# design.net
KiCad netlist of a schematic drawn in Altium Designer
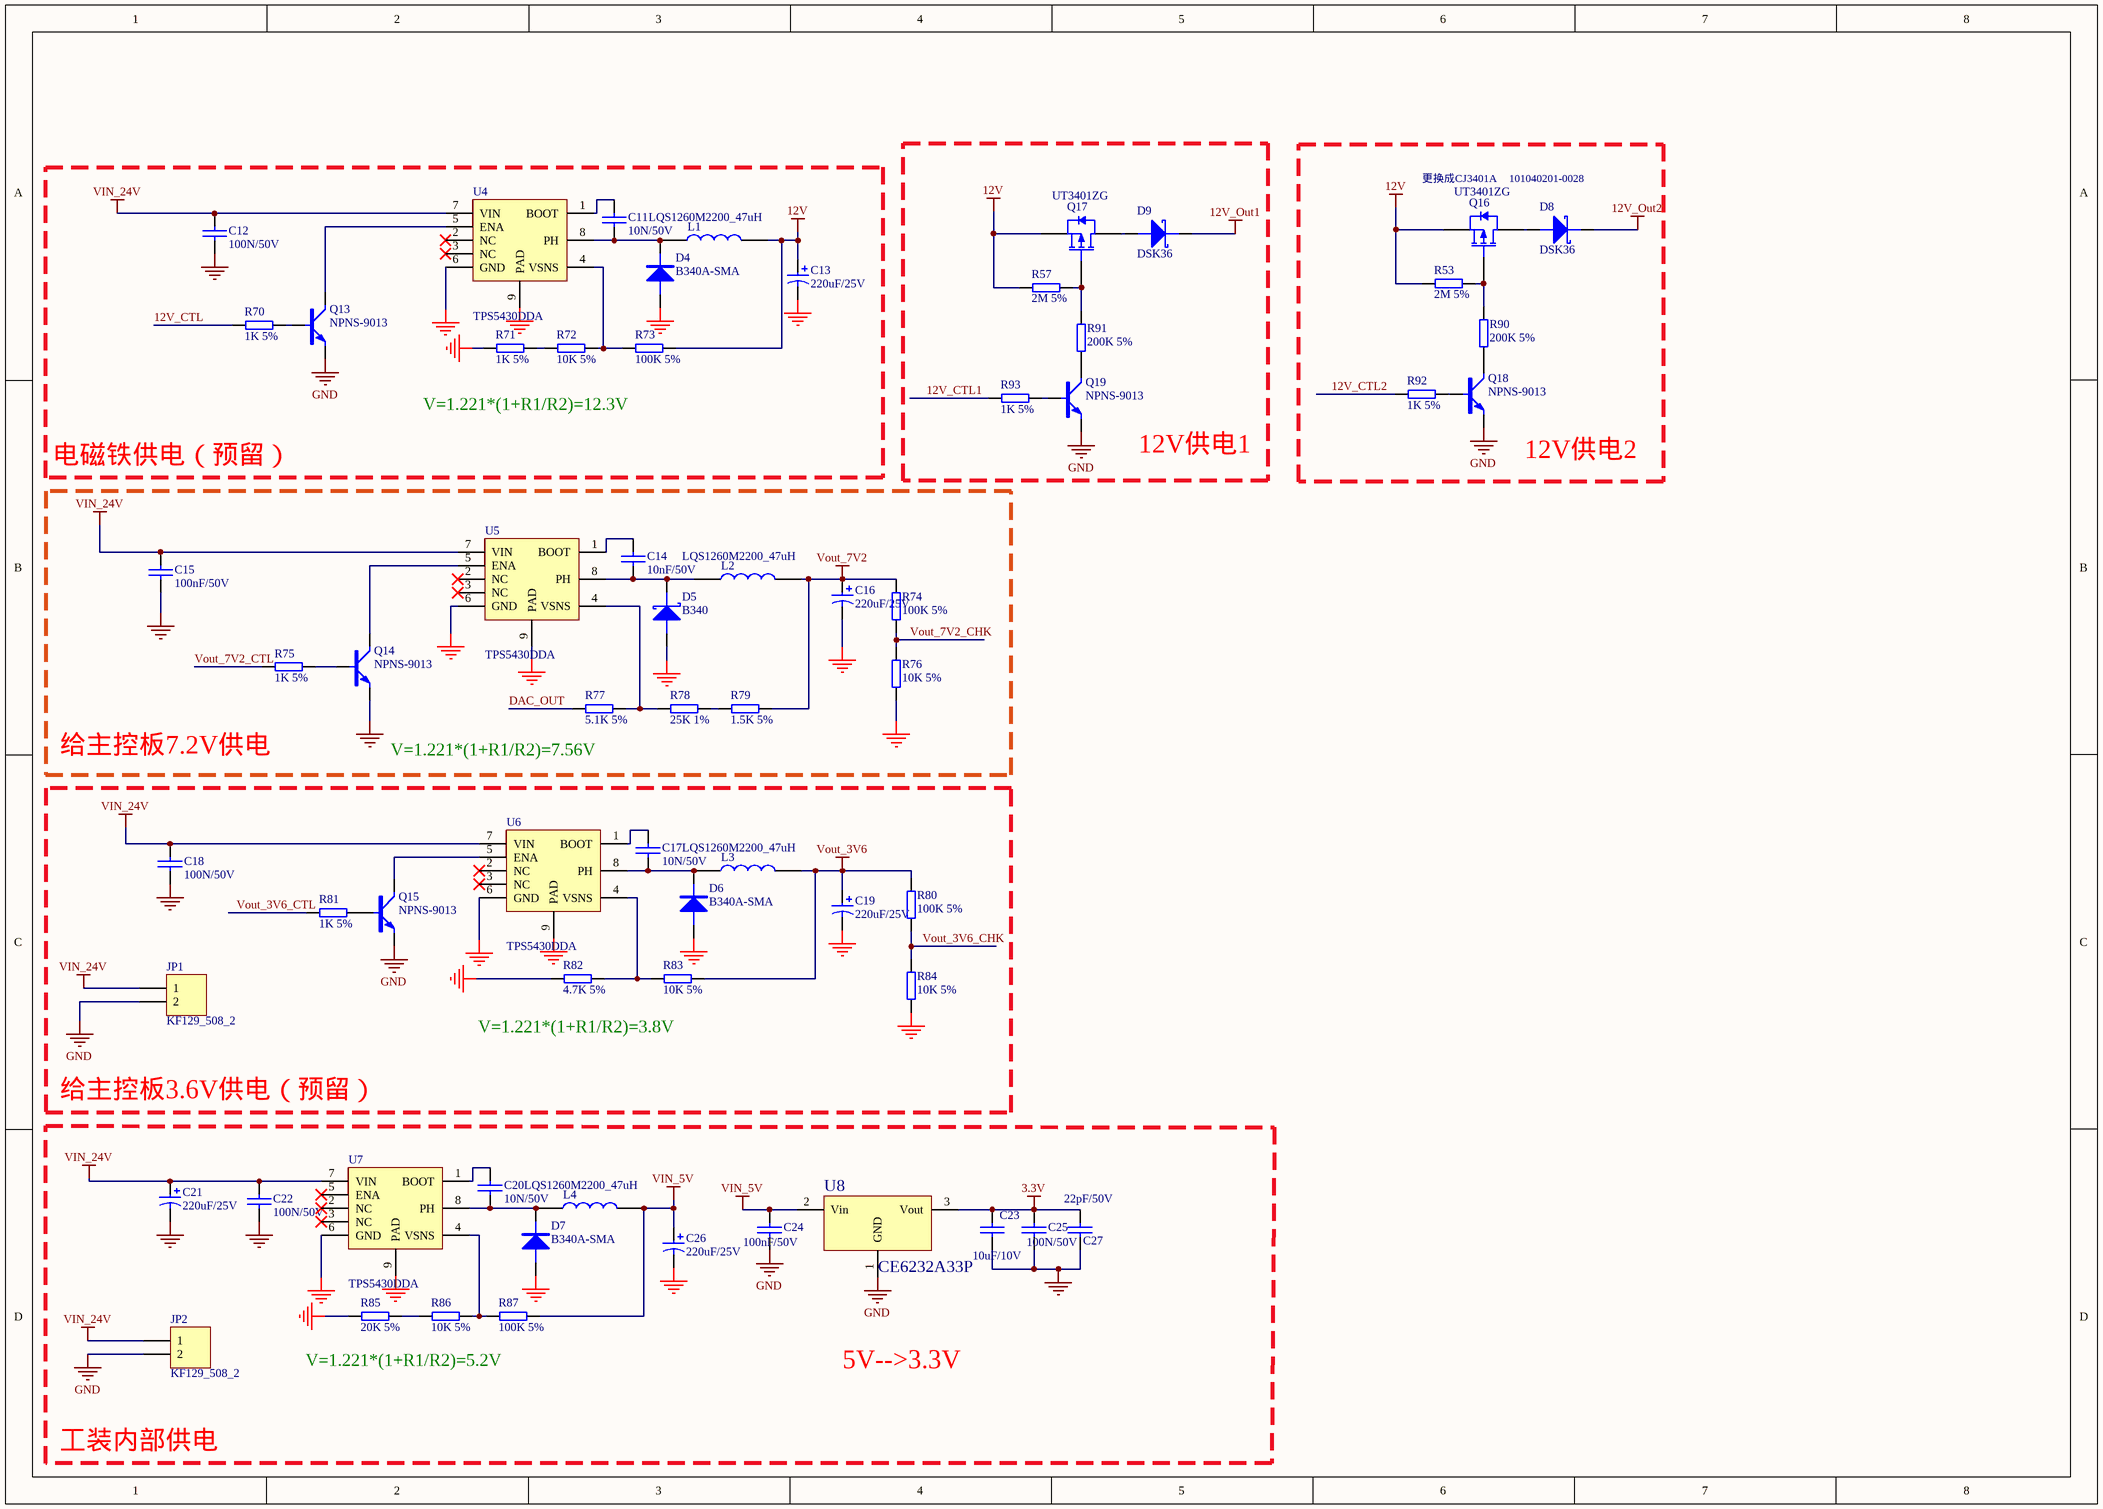
[diagram p0: 电源.SchDoc]

(export (version "E")
  (design (tool "Eeschema 10.0.6"))
  (components
    (comp (ref "C11")
      (value "10N/50V")
      (footprint "CAP0603")
      (description "10N/50V，±10%，0603")
      (fields (field (name "PART NUMBER") "101020103-0007"))
      (libsource (lib "Database_Libs1") (part "CC03K7R9B_10N"))
    )
    (comp (ref "C12")
      (value "100N/50V")
      (footprint "CAP0603")
      (description "100N/50V，±10%，0603")
      (fields (field (name "PART NUMBER") "101020103-0021"))
      (libsource (lib "Database_Libs1") (part "CC03K7R9B_100N"))
    )
    (comp (ref "C13")
      (value "220uF/25V")
      (footprint "220uF 25V")
      (description "220UF,25 V,±20%,8*10mm,立隆电子工业股份有限公司,VEJ221M1ETR-0810")
      (libsource (lib "转接板封装") (part "220uF/25V"))
    )
    (comp (ref "C14")
      (value "10nF/50V")
      (footprint "CAP0603")
      (description "10nF,50 V,±10%,0603,X7R,国巨,CC0603KRX7R9BB103")
      (fields (field (name "PART NUMBER") "101020103-0007"))
      (libsource (lib "Database_Libs2") (part "CC03K7R9_103P"))
    )
    (comp (ref "C15")
      (value "100nF/50V")
      (footprint "CAP0603")
      (description "104pF,50 V,±10%,0603,国巨,CC0603KRX7R9BB104")
      (fields (field (name "PART NUMBER") "101020103-0021"))
      (libsource (lib "Database_Libs2") (part "CC03K7R9_100N"))
    )
    (comp (ref "C16")
      (value "220uF/25V")
      (footprint "220uF 25V")
      (description "220UF,25 V,±20%,8*10mm,立隆电子工业股份有限公司,VEJ221M1ETR-0810")
      (libsource (lib "转接板封装") (part "220uF/25V"))
    )
    (comp (ref "C17")
      (value "10N/50V")
      (footprint "CAP0603")
      (description "10N/50V，±10%，0603")
      (fields (field (name "PART NUMBER") "101020103-0007"))
      (libsource (lib "Database_Libs1") (part "CC03K7R9B_10N"))
    )
    (comp (ref "C18")
      (value "100N/50V")
      (footprint "CAP0603")
      (description "100N/50V，±10%，0603")
      (fields (field (name "PART NUMBER") "101020103-0021"))
      (libsource (lib "Database_Libs1") (part "CC03K7R9B_100N"))
    )
    (comp (ref "C19")
      (value "220uF/25V")
      (footprint "220uF 25V")
      (description "220UF,25 V,±20%,8*10mm,立隆电子工业股份有限公司,VEJ221M1ETR-0810")
      (libsource (lib "转接板封装") (part "220uF/25V"))
    )
    (comp (ref "C20")
      (value "10N/50V")
      (footprint "CAP0603")
      (description "10N/50V，±10%，0603")
      (fields (field (name "PART NUMBER") "101020103-0007"))
      (libsource (lib "Database_Libs1") (part "CC03K7R9B_10N"))
    )
    (comp (ref "C21")
      (value "220uF/25V")
      (footprint "220uF 25V")
      (description "220UF,25 V,±20%,8*10mm,立隆电子工业股份有限公司,VEJ221M1ETR-0810")
      (libsource (lib "转接板封装") (part "220uF/25V"))
    )
    (comp (ref "C22")
      (value "100N/50V")
      (footprint "CAP0603")
      (description "100N/50V，±10%，0603")
      (fields (field (name "PART NUMBER") "101020103-0021"))
      (libsource (lib "Database_Libs1") (part "CC03K7R9B_100N"))
    )
    (comp (ref "C23")
      (value "10uF/10V")
      (footprint "CAP0603")
      (description "106pF,10 V,±10%,0603,村田,GRM188R61A106KE47D")
      (fields (field (name "PART NUMBER") "101020103-0026"))
      (libsource (lib "Database_Libs2") (part "CC03K5R6_10U"))
    )
    (comp (ref "C24")
      (value "100nF/50V")
      (footprint "CAP0603")
      (description "104pF,50 V,±10%,0603,国巨,CC0603KRX7R9BB104")
      (fields (field (name "PART NUMBER") "101020103-0021"))
      (libsource (lib "Database_Libs2") (part "CC03K7R9_100N"))
    )
    (comp (ref "C25")
      (value "100N/50V")
      (footprint "CAP0603")
      (description "100N/50V，±10%，0603")
      (fields (field (name "PART NUMBER") "101020103-0021"))
      (libsource (lib "Database_Libs2") (part "CC03K7R9B_100N"))
    )
    (comp (ref "C26")
      (value "220uF/25V")
      (footprint "220uF 25V")
      (description "220UF,25 V,±20%,8*10mm,立隆电子工业股份有限公司,VEJ221M1ETR-0810")
      (libsource (lib "转接板封装") (part "220uF/25V"))
    )
    (comp (ref "C27")
      (value "22pF/50V")
      (footprint "CAP0603")
      (description "22pF,50 V,±5%,0603,国巨,CC0603JRNPO9BN22")
      (fields (field (name "PART NUMBER") "101020103-0009"))
      (libsource (lib "Database_Libs2") (part "CC03JPO9_22P"))
    )
    (comp (ref "D4")
      (value "B340A-SMA")
      (footprint "DO-214AC")
      (fields (field (name "PART NUMBER") "101040101-0014"))
      (libsource (lib "Database_Libs1") (part "02_B340A-SMA"))
    )
    (comp (ref "D5")
      (value "B340")
      (footprint "DO-214AC")
      (description "B340,SMA,3 A,0.7 V,28 V,DIODES,B340A-13-F")
      (fields (field (name "PART NUMBER") "101040101-0014"))
      (libsource (lib "Database_Libs2") (part "02_B340"))
    )
    (comp (ref "D6")
      (value "B340A-SMA")
      (footprint "DO-214AC")
      (fields (field (name "PART NUMBER") "101040101-0014"))
      (libsource (lib "Database_Libs1") (part "02_B340A-SMA"))
    )
    (comp (ref "D7")
      (value "B340A-SMA")
      (footprint "DO-214AC")
      (fields (field (name "PART NUMBER") "101040101-0014"))
      (libsource (lib "Database_Libs1") (part "02_B340A-SMA"))
    )
    (comp (ref "D8")
      (value "DSK36")
      (footprint "SOD-123FL")
      (description "DSK14,SOD-123FL,1 A,40 V,28 V,台湾强茂集团苏州群鑫电子,DSK14")
      (fields (field (name "PART NUMBER") "101040101-0043"))
      (libsource (lib "Database_Libs2") (part "02_DSK14"))
    )
    (comp (ref "D9")
      (value "DSK36")
      (footprint "SOD-123FL")
      (description "DSK14,SOD-123FL,1 A,40 V,28 V,台湾强茂集团苏州群鑫电子,DSK14")
      (fields (field (name "PART NUMBER") "101040101-0043"))
      (libsource (lib "Database_Libs2") (part "02_DSK14"))
    )
    (comp (ref "JP1")
      (value "KF129_508_2")
      (footprint "KF129_508_2")
      (description "KF129-2P,螺丝紧固,2,ABS,松涛")
      (fields (field (name "PART NUMBER") "1010904-0015"))
      (libsource (lib "Database_Libs2") (part "KF129_508_2"))
    )
    (comp (ref "JP2")
      (value "KF129_508_2")
      (footprint "KF129_508_2")
      (description "KF129-2P,螺丝紧固,2,ABS,松涛")
      (fields (field (name "PART NUMBER") "1010904-0015"))
      (libsource (lib "Database_Libs2") (part "KF129_508_2"))
    )
    (comp (ref "L1")
      (value "LQS1260M2200_47uH")
      (footprint "LQS1212")
      (description "47uH/2.2A,±20%，0.072Ω，L1200X1200X600")
      (fields (field (name "PART NUMBER") "1010302-0007"))
      (libsource (lib "Database_Libs1") (part "06_LQS1260M2200_47uH"))
    )
    (comp (ref "L2")
      (value "LQS1260M2200_47uH")
      (footprint "LQS1212")
      (description "47uH/2.2A,±20%，0.072Ω，L1200X1200X600")
      (fields (field (name "PART NUMBER") "1010302-0007"))
      (libsource (lib "Database_Libs1") (part "06_LQS1260M2200_47uH"))
    )
    (comp (ref "L3")
      (value "LQS1260M2200_47uH")
      (footprint "LQS1212")
      (description "47uH/2.2A,±20%，0.072Ω，L1200X1200X600")
      (fields (field (name "PART NUMBER") "1010302-0007"))
      (libsource (lib "Database_Libs1") (part "06_LQS1260M2200_47uH"))
    )
    (comp (ref "L4")
      (value "LQS1260M2200_47uH")
      (footprint "LQS1212")
      (description "47uH/2.2A,±20%，0.072Ω，L1200X1200X600")
      (fields (field (name "PART NUMBER") "1010302-0007"))
      (libsource (lib "Database_Libs1") (part "06_LQS1260M2200_47uH"))
    )
    (comp (ref "Q13")
      (value "NPNS-9013")
      (footprint "SOT-23")
      (description "9013,NPN,SOT-23,长电,S9013")
      (fields (field (name "PART NUMBER") "101040201-0002"))
      (libsource (lib "Database_Libs2") (part "03_NPNS-9013"))
    )
    (comp (ref "Q14")
      (value "NPNS-9013")
      (footprint "SOT-23")
      (description "9013,NPN,SOT-23,长电,S9013")
      (fields (field (name "PART NUMBER") "101040201-0002"))
      (libsource (lib "Database_Libs2") (part "03_NPNS-9013"))
    )
    (comp (ref "Q15")
      (value "NPNS-9013")
      (footprint "SOT-23")
      (description "9013,NPN,SOT-23,长电,S9013")
      (fields (field (name "PART NUMBER") "101040201-0002"))
      (libsource (lib "Database_Libs2") (part "03_NPNS-9013"))
    )
    (comp (ref "Q16")
      (value "UT3401ZG")
      (footprint "SOT-23")
      (description "UT3401ZG,P-MOS,SOT-23,UTC,UT3401ZG")
      (fields (field (name "PART NUMBER") "101040201-0013"))
      (libsource (lib "Database_Libs2") (part "03_P-UT3401ZG"))
    )
    (comp (ref "Q17")
      (value "UT3401ZG")
      (footprint "SOT-23")
      (description "UT3401ZG,P-MOS,SOT-23,UTC,UT3401ZG")
      (fields (field (name "PART NUMBER") "101040201-0013"))
      (libsource (lib "Database_Libs2") (part "03_P-UT3401ZG"))
    )
    (comp (ref "Q18")
      (value "NPNS-9013")
      (footprint "SOT-23")
      (description "9013,NPN,SOT-23,长电,S9013")
      (fields (field (name "PART NUMBER") "101040201-0002"))
      (libsource (lib "Database_Libs2") (part "03_NPNS-9013"))
    )
    (comp (ref "Q19")
      (value "NPNS-9013")
      (footprint "SOT-23")
      (description "9013,NPN,SOT-23,长电,S9013")
      (fields (field (name "PART NUMBER") "101040201-0002"))
      (libsource (lib "Database_Libs2") (part "03_NPNS-9013"))
    )
    (comp (ref "R53")
      (value "2M 5%")
      (footprint "RES0603")
      (description "国巨,±5%,0603,,155 ℃,-55 ℃,RC0603JR-072ML,含铅,100 ppm/℃,1/10W,,2M")
      (fields (field (name "PART NUMBER") "101010103-0025"))
      (libsource (lib "Database_Libs2") (part "RC03J_2M"))
    )
    (comp (ref "R57")
      (value "2M 5%")
      (footprint "RES0603")
      (description "国巨,±5%,0603,,155 ℃,-55 ℃,RC0603JR-072ML,含铅,100 ppm/℃,1/10W,,2M")
      (fields (field (name "PART NUMBER") "101010103-0025"))
      (libsource (lib "Database_Libs2") (part "RC03J_2M"))
    )
    (comp (ref "R70")
      (value "1K 5%")
      (footprint "RES0603")
      (description "1K,±5%,1/10W,0603,国巨,RC0603JR-071KL")
      (fields (field (name "PART NUMBER") "101010103-0008"))
      (libsource (lib "Database_Libs2") (part "RC03J_1K"))
    )
    (comp (ref "R71")
      (value "1K 5%")
      (footprint "RES0603")
      (description "1K,±5%,1/10W,0603,国巨,RC0603JR-071KL")
      (fields (field (name "PART NUMBER") "101010103-0008"))
      (libsource (lib "Database_Libs2") (part "RC03J_1K"))
    )
    (comp (ref "R72")
      (value "10K 5%")
      (footprint "RES0603")
      (description "国巨,±5%,0603,,155 ℃,-55 ℃,RC0603JR-0710KL,无铅,200 ppm/℃,1/10W,,10K")
      (fields (field (name "PART NUMBER") "101010103-0003"))
      (libsource (lib "Database_Libs2") (part "RC03J_10K"))
    )
    (comp (ref "R73")
      (value "100K 5%")
      (footprint "RES0603")
      (description "国巨,±5%,0603,,155 ℃,-55 ℃,RC0603JR-07100KL,无铅,100 ppm/℃,1/10W,,100K")
      (fields (field (name "PART NUMBER") "101010103-0005"))
      (libsource (lib "Database_Libs2") (part "RC03J_100K"))
    )
    (comp (ref "R74")
      (value "100K 5%")
      (footprint "RES0603")
      (description "国巨,±5%,0603,,155 ℃,-55 ℃,RC0603JR-07100KL,无铅,100 ppm/℃,1/10W,,100K")
      (fields (field (name "PART NUMBER") "101010103-0005"))
      (libsource (lib "Database_Libs2") (part "RC03J_100K"))
    )
    (comp (ref "R75")
      (value "1K 5%")
      (footprint "RES0603")
      (description "1K,±5%,1/10W,0603,国巨,RC0603JR-071KL")
      (fields (field (name "PART NUMBER") "101010103-0008"))
      (libsource (lib "Database_Libs2") (part "RC03J_1K"))
    )
    (comp (ref "R76")
      (value "10K 5%")
      (footprint "RES0603")
      (description "国巨,±5%,0603,,155 ℃,-55 ℃,RC0603JR-0710KL,无铅,200 ppm/℃,1/10W,,10K")
      (fields (field (name "PART NUMBER") "101010103-0003"))
      (libsource (lib "Database_Libs2") (part "RC03J_10K"))
    )
    (comp (ref "R77")
      (value "5.1K 5%")
      (footprint "RES0603")
      (description "国巨,±5%,0603,,155 ℃,55 ℃,RC0603JR-075.1KL,无铅,200 ppm/℃,1/10W,,5.1k")
      (fields (field (name "PART NUMBER") "101010103-0015"))
      (libsource (lib "Database_Libs2") (part "RC03J_5.1K"))
    )
    (comp (ref "R78")
      (value "25K 1%")
      (footprint "RES0603")
      (description "25K±1%,1/10W,0603")
      (fields (field (name "PART NUMBER") "101010103-0056"))
      (libsource (lib "转接板封装") (part "RC03J_25K"))
    )
    (comp (ref "R79")
      (value "1.5K 5%")
      (footprint "RES0603")
      (description "1.5K,±5%,1/10W,0603,国巨,RC0603JR-071K5L")
      (fields (field (name "PART NUMBER") "101010103-0013"))
      (libsource (lib "转接板封装") (part "RC03J_1.5K"))
    )
    (comp (ref "R80")
      (value "100K 5%")
      (footprint "RES0603")
      (description "100K±5%,1/10W,0603")
      (fields (field (name "PART NUMBER") "101010103-0005"))
      (libsource (lib "Database_Libs1") (part "RC03JF_100K"))
    )
    (comp (ref "R81")
      (value "1K 5%")
      (footprint "RES0603")
      (description "1K,±5%,1/10W,0603,国巨,RC0603JR-071KL")
      (fields (field (name "PART NUMBER") "101010103-0008"))
      (libsource (lib "Database_Libs2") (part "RC03J_1K"))
    )
    (comp (ref "R82")
      (value "4.7K 5%")
      (footprint "RES0603")
      (description "4.7K±5%,1/10W,0603")
      (fields (field (name "PART NUMBER") "101010103-0042"))
      (libsource (lib "Database_Libs2") (part "RC03J_4.7K"))
    )
    (comp (ref "R83")
      (value "10K 5%")
      (footprint "RES0603")
      (description "国巨,±5%,0603,,155 ℃,-55 ℃,RC0603JR-0710KL,无铅,200 ppm/℃,1/10W,,10K")
      (fields (field (name "PART NUMBER") "101010103-0003"))
      (libsource (lib "Database_Libs2") (part "RC03J_10K"))
    )
    (comp (ref "R84")
      (value "10K 5%")
      (footprint "RES0603")
      (description "国巨,±5%,0603,,155 ℃,-55 ℃,RC0603JR-0710KL,无铅,200 ppm/℃,1/10W,,10K")
      (fields (field (name "PART NUMBER") "101010103-0003"))
      (libsource (lib "Database_Libs2") (part "RC03J_10K"))
    )
    (comp (ref "R85")
      (value "20K 5%")
      (footprint "RES0603")
      (description "国巨,±5%,0603,,155 ℃,-55 ℃,RC0603JR-0720KL,无铅,200 ppm/℃,1/10W,,20K")
      (fields (field (name "PART NUMBER") "101010103-0004"))
      (libsource (lib "Database_Libs2") (part "RC03J_20K"))
    )
    (comp (ref "R86")
      (value "10K 5%")
      (footprint "RES0603")
      (description "国巨,±5%,0603,,155 ℃,-55 ℃,RC0603JR-0710KL,无铅,200 ppm/℃,1/10W,,10K")
      (fields (field (name "PART NUMBER") "101010103-0003"))
      (libsource (lib "Database_Libs2") (part "RC03J_10K"))
    )
    (comp (ref "R87")
      (value "100K 5%")
      (footprint "RES0603")
      (description "100K±5%,1/10W,0603")
      (fields (field (name "PART NUMBER") "101010103-0005"))
      (libsource (lib "Database_Libs1") (part "RC03JF_100K"))
    )
    (comp (ref "R90")
      (value "200K 5%")
      (footprint "RES0603")
      (description "200K,±5%,1/10W,0603,国巨,RC0603JR-07200KL")
      (fields (field (name "PART NUMBER") "101010103-0034"))
      (libsource (lib "Database_Libs2") (part "RC03J_200K"))
    )
    (comp (ref "R91")
      (value "200K 5%")
      (footprint "RES0603")
      (description "200K,±5%,1/10W,0603,国巨,RC0603JR-07200KL")
      (fields (field (name "PART NUMBER") "101010103-0034"))
      (libsource (lib "Database_Libs2") (part "RC03J_200K"))
    )
    (comp (ref "R92")
      (value "1K 5%")
      (footprint "RES0603")
      (description "1K,±5%,1/10W,0603,国巨,RC0603JR-071KL")
      (fields (field (name "PART NUMBER") "101010103-0008"))
      (libsource (lib "Database_Libs2") (part "RC03J_1K"))
    )
    (comp (ref "R93")
      (value "1K 5%")
      (footprint "RES0603")
      (description "1K,±5%,1/10W,0603,国巨,RC0603JR-071KL")
      (fields (field (name "PART NUMBER") "101010103-0008"))
      (libsource (lib "Database_Libs2") (part "RC03J_1K"))
    )
    (comp (ref "U4")
      (value "TPS5430DDA")
      (footprint "SOP-8-P")
      (description "TPS5430DDA,SOP8,TI,TPS5430DDA")
      (fields (field (name "PART NUMBER") "101050101-0053"))
      (libsource (lib "Database_Libs2") (part "02_TPS5430DDA"))
    )
    (comp (ref "U5")
      (value "TPS5430DDA")
      (footprint "SOP-8-P")
      (description "TPS5430DDA,SOP8,TI,TPS5430DDA")
      (fields (field (name "PART NUMBER") "101050101-0053"))
      (libsource (lib "Database_Libs2") (part "02_TPS5430DDA"))
    )
    (comp (ref "U6")
      (value "TPS5430DDA")
      (footprint "SOP-8-P")
      (description "TPS5430DDA,SOP8,TI,TPS5430DDA")
      (fields (field (name "PART NUMBER") "101050101-0053"))
      (libsource (lib "Database_Libs2") (part "02_TPS5430DDA"))
    )
    (comp (ref "U7")
      (value "TPS5430DDA")
      (footprint "SOP-8-P")
      (description "TPS5430DDA,SOP8,TI,TPS5430DDA")
      (fields (field (name "PART NUMBER") "101050101-0053"))
      (libsource (lib "Database_Libs2") (part "02_TPS5430DDA"))
    )
    (comp (ref "U8")
      (value "CE6232A33P")
      (footprint "SOT-89")
      (description "CE6232-3.3,CE6232-3.3,SOT89-3,8V,1.8V,0.11V,3.3V,300mA,0.8uA,南京芯力微电子有限公司")
      (fields (field (name "PART NUMBER") "1010503-0029"))
      (libsource (lib "Database_Libs2") (part "02_CE6232A33P"))
    )
  )
  (nets
    (net (code "1") (name "/12V_CTL") (class "Default")
      (node (ref "R70") (pin "1") (pinfunction "1_1") (pintype "passive"))
    )
    (net (code "2") (name "/12V_CTL1") (class "Default")
      (node (ref "R93") (pin "1") (pinfunction "1_1") (pintype "passive"))
    )
    (net (code "3") (name "/12V_CTL2") (class "Default")
      (node (ref "R92") (pin "1") (pinfunction "1_1") (pintype "passive"))
    )
    (net (code "4") (name "/DAC_OUT") (class "Default")
      (node (ref "R77") (pin "1") (pinfunction "1_1") (pintype "passive"))
    )
    (net (code "5") (name "/Vout_3V6_CHK") (class "Default")
      (node (ref "R80") (pin "1") (pinfunction "1_1") (pintype "passive"))
      (node (ref "R84") (pin "2") (pinfunction "2_2") (pintype "passive"))
    )
    (net (code "6") (name "/Vout_3V6_CTL") (class "Default")
      (node (ref "R81") (pin "1") (pinfunction "1_1") (pintype "passive"))
    )
    (net (code "7") (name "/Vout_7V2_CHK") (class "Default")
      (node (ref "R74") (pin "1") (pinfunction "1_1") (pintype "passive"))
      (node (ref "R76") (pin "2") (pinfunction "2_2") (pintype "passive"))
    )
    (net (code "8") (name "/Vout_7V2_CTL") (class "Default")
      (node (ref "R75") (pin "1") (pinfunction "1_1") (pintype "passive"))
    )
    (net (code "9") (name "3.3V") (class "Default")
      (node (ref "C23") (pin "1") (pinfunction "1_1") (pintype "passive"))
      (node (ref "C25") (pin "1") (pinfunction "1_1") (pintype "passive"))
      (node (ref "C27") (pin "1") (pinfunction "1_1") (pintype "passive"))
      (node (ref "U8") (pin "3") (pinfunction "Vout_3") (pintype "passive"))
    )
    (net (code "10") (name "12V") (class "Default")
      (node (ref "C13") (pin "1") (pinfunction "1_1") (pintype "passive"))
      (node (ref "L1") (pin "2") (pinfunction "2_2") (pintype "passive"))
      (node (ref "Q16") (pin "2") (pinfunction "S_2") (pintype "passive"))
      (node (ref "Q17") (pin "2") (pinfunction "S_2") (pintype "passive"))
      (node (ref "R53") (pin "1") (pinfunction "1_1") (pintype "passive"))
      (node (ref "R57") (pin "1") (pinfunction "1_1") (pintype "passive"))
      (node (ref "R73") (pin "2") (pinfunction "2_2") (pintype "passive"))
    )
    (net (code "11") (name "12V_Out1") (class "Default")
      (node (ref "D9") (pin "2") (pinfunction "2_2") (pintype "passive"))
    )
    (net (code "12") (name "12V_Out2") (class "Default")
      (node (ref "D8") (pin "2") (pinfunction "2_2") (pintype "passive"))
    )
    (net (code "13") (name "GND") (class "Default")
      (node (ref "C12") (pin "2") (pinfunction "2_2") (pintype "passive"))
      (node (ref "C13") (pin "2") (pinfunction "2_2") (pintype "passive"))
      (node (ref "C15") (pin "2") (pinfunction "2_2") (pintype "passive"))
      (node (ref "C16") (pin "2") (pinfunction "2_2") (pintype "passive"))
      (node (ref "C18") (pin "2") (pinfunction "2_2") (pintype "passive"))
      (node (ref "C19") (pin "2") (pinfunction "2_2") (pintype "passive"))
      (node (ref "C21") (pin "2") (pinfunction "2_2") (pintype "passive"))
      (node (ref "C22") (pin "2") (pinfunction "2_2") (pintype "passive"))
      (node (ref "C23") (pin "2") (pinfunction "2_2") (pintype "passive"))
      (node (ref "C24") (pin "2") (pinfunction "2_2") (pintype "passive"))
      (node (ref "C25") (pin "2") (pinfunction "2_2") (pintype "passive"))
      (node (ref "C26") (pin "2") (pinfunction "2_2") (pintype "passive"))
      (node (ref "C27") (pin "2") (pinfunction "2_2") (pintype "passive"))
      (node (ref "D4") (pin "1") (pinfunction "1_1") (pintype "passive"))
      (node (ref "D5") (pin "1") (pinfunction "1_1") (pintype "passive"))
      (node (ref "D6") (pin "1") (pinfunction "1_1") (pintype "passive"))
      (node (ref "D7") (pin "1") (pinfunction "1_1") (pintype "passive"))
      (node (ref "JP1") (pin "2") (pinfunction "2_2") (pintype "passive"))
      (node (ref "JP2") (pin "2") (pinfunction "2_2") (pintype "passive"))
      (node (ref "Q13") (pin "2") (pinfunction "E_2") (pintype "passive"))
      (node (ref "Q14") (pin "2") (pinfunction "E_2") (pintype "passive"))
      (node (ref "Q15") (pin "2") (pinfunction "E_2") (pintype "passive"))
      (node (ref "Q18") (pin "2") (pinfunction "E_2") (pintype "passive"))
      (node (ref "Q19") (pin "2") (pinfunction "E_2") (pintype "passive"))
      (node (ref "R71") (pin "1") (pinfunction "1_1") (pintype "passive"))
      (node (ref "R76") (pin "1") (pinfunction "1_1") (pintype "passive"))
      (node (ref "R82") (pin "1") (pinfunction "1_1") (pintype "passive"))
      (node (ref "R84") (pin "1") (pinfunction "1_1") (pintype "passive"))
      (node (ref "R85") (pin "1") (pinfunction "1_1") (pintype "passive"))
      (node (ref "U4") (pin "6") (pinfunction "GND_6") (pintype "passive"))
      (node (ref "U4") (pin "9") (pinfunction "PAD_9") (pintype "passive"))
      (node (ref "U5") (pin "6") (pinfunction "GND_6") (pintype "passive"))
      (node (ref "U5") (pin "9") (pinfunction "PAD_9") (pintype "passive"))
      (node (ref "U6") (pin "6") (pinfunction "GND_6") (pintype "passive"))
      (node (ref "U6") (pin "9") (pinfunction "PAD_9") (pintype "passive"))
      (node (ref "U7") (pin "6") (pinfunction "GND_6") (pintype "passive"))
      (node (ref "U7") (pin "9") (pinfunction "PAD_9") (pintype "passive"))
      (node (ref "U8") (pin "1") (pinfunction "GND_1") (pintype "passive"))
    )
    (net (code "14") (name "Net-(Q13-B)") (class "Default")
      (node (ref "Q13") (pin "1") (pinfunction "B_1") (pintype "passive"))
      (node (ref "R70") (pin "2") (pinfunction "2_2") (pintype "passive"))
    )
    (net (code "15") (name "Net-(Q13-C)") (class "Default")
      (node (ref "Q13") (pin "3") (pinfunction "C_3") (pintype "passive"))
      (node (ref "U4") (pin "5") (pinfunction "ENA_5") (pintype "passive"))
    )
    (net (code "16") (name "Net-(Q14-B)") (class "Default")
      (node (ref "Q14") (pin "1") (pinfunction "B_1") (pintype "passive"))
      (node (ref "R75") (pin "2") (pinfunction "2_2") (pintype "passive"))
    )
    (net (code "17") (name "Net-(Q14-C)") (class "Default")
      (node (ref "Q14") (pin "3") (pinfunction "C_3") (pintype "passive"))
      (node (ref "U5") (pin "5") (pinfunction "ENA_5") (pintype "passive"))
    )
    (net (code "18") (name "Net-(Q15-B)") (class "Default")
      (node (ref "Q15") (pin "1") (pinfunction "B_1") (pintype "passive"))
      (node (ref "R81") (pin "2") (pinfunction "2_2") (pintype "passive"))
    )
    (net (code "19") (name "Net-(Q15-C)") (class "Default")
      (node (ref "Q15") (pin "3") (pinfunction "C_3") (pintype "passive"))
      (node (ref "U6") (pin "5") (pinfunction "ENA_5") (pintype "passive"))
    )
    (net (code "20") (name "Net-(Q16-D)") (class "Default")
      (node (ref "D8") (pin "1") (pinfunction "1_1") (pintype "passive"))
      (node (ref "Q16") (pin "3") (pinfunction "D_3") (pintype "passive"))
    )
    (net (code "21") (name "Net-(Q16-G)") (class "Default")
      (node (ref "Q16") (pin "1") (pinfunction "G_1") (pintype "passive"))
      (node (ref "R53") (pin "2") (pinfunction "2_2") (pintype "passive"))
      (node (ref "R90") (pin "2") (pinfunction "2_2") (pintype "passive"))
    )
    (net (code "22") (name "Net-(Q17-D)") (class "Default")
      (node (ref "D9") (pin "1") (pinfunction "1_1") (pintype "passive"))
      (node (ref "Q17") (pin "3") (pinfunction "D_3") (pintype "passive"))
    )
    (net (code "23") (name "Net-(Q17-G)") (class "Default")
      (node (ref "Q17") (pin "1") (pinfunction "G_1") (pintype "passive"))
      (node (ref "R57") (pin "2") (pinfunction "2_2") (pintype "passive"))
      (node (ref "R91") (pin "2") (pinfunction "2_2") (pintype "passive"))
    )
    (net (code "24") (name "Net-(Q18-B)") (class "Default")
      (node (ref "Q18") (pin "1") (pinfunction "B_1") (pintype "passive"))
      (node (ref "R92") (pin "2") (pinfunction "2_2") (pintype "passive"))
    )
    (net (code "25") (name "Net-(Q18-C)") (class "Default")
      (node (ref "Q18") (pin "3") (pinfunction "C_3") (pintype "passive"))
      (node (ref "R90") (pin "1") (pinfunction "1_1") (pintype "passive"))
    )
    (net (code "26") (name "Net-(Q19-B)") (class "Default")
      (node (ref "Q19") (pin "1") (pinfunction "B_1") (pintype "passive"))
      (node (ref "R93") (pin "2") (pinfunction "2_2") (pintype "passive"))
    )
    (net (code "27") (name "Net-(Q19-C)") (class "Default")
      (node (ref "Q19") (pin "3") (pinfunction "C_3") (pintype "passive"))
      (node (ref "R91") (pin "1") (pinfunction "1_1") (pintype "passive"))
    )
    (net (code "28") (name "Net-(R71-Pad2)") (class "Default")
      (node (ref "R71") (pin "2") (pinfunction "2_2") (pintype "passive"))
      (node (ref "R72") (pin "1") (pinfunction "1_1") (pintype "passive"))
    )
    (net (code "29") (name "Net-(R78-Pad2)") (class "Default")
      (node (ref "R78") (pin "2") (pinfunction "2_2") (pintype "passive"))
      (node (ref "R79") (pin "1") (pinfunction "1_1") (pintype "passive"))
    )
    (net (code "30") (name "Net-(R85-Pad2)") (class "Default")
      (node (ref "R85") (pin "2") (pinfunction "2_2") (pintype "passive"))
      (node (ref "R86") (pin "1") (pinfunction "1_1") (pintype "passive"))
    )
    (net (code "31") (name "Net-(U4-BOOT)") (class "Default")
      (node (ref "C11") (pin "2") (pinfunction "2_2") (pintype "passive"))
      (node (ref "U4") (pin "1") (pinfunction "BOOT_1") (pintype "passive"))
    )
    (net (code "32") (name "Net-(U4-PH)") (class "Default")
      (node (ref "C11") (pin "1") (pinfunction "1_1") (pintype "passive"))
      (node (ref "D4") (pin "2") (pinfunction "2_2") (pintype "passive"))
      (node (ref "L1") (pin "1") (pinfunction "1_1") (pintype "passive"))
      (node (ref "U4") (pin "8") (pinfunction "PH_8") (pintype "passive"))
    )
    (net (code "33") (name "Net-(U4-VSNS)") (class "Default")
      (node (ref "R72") (pin "2") (pinfunction "2_2") (pintype "passive"))
      (node (ref "R73") (pin "1") (pinfunction "1_1") (pintype "passive"))
      (node (ref "U4") (pin "4") (pinfunction "VSNS_4") (pintype "passive"))
    )
    (net (code "34") (name "Net-(U5-BOOT)") (class "Default")
      (node (ref "C14") (pin "2") (pinfunction "2_2") (pintype "passive"))
      (node (ref "U5") (pin "1") (pinfunction "BOOT_1") (pintype "passive"))
    )
    (net (code "35") (name "Net-(U5-PH)") (class "Default")
      (node (ref "C14") (pin "1") (pinfunction "1_1") (pintype "passive"))
      (node (ref "D5") (pin "2") (pinfunction "2_2") (pintype "passive"))
      (node (ref "L2") (pin "1") (pinfunction "1_1") (pintype "passive"))
      (node (ref "U5") (pin "8") (pinfunction "PH_8") (pintype "passive"))
    )
    (net (code "36") (name "Net-(U5-VSNS)") (class "Default")
      (node (ref "R77") (pin "2") (pinfunction "2_2") (pintype "passive"))
      (node (ref "R78") (pin "1") (pinfunction "1_1") (pintype "passive"))
      (node (ref "U5") (pin "4") (pinfunction "VSNS_4") (pintype "passive"))
    )
    (net (code "37") (name "Net-(U6-BOOT)") (class "Default")
      (node (ref "C17") (pin "2") (pinfunction "2_2") (pintype "passive"))
      (node (ref "U6") (pin "1") (pinfunction "BOOT_1") (pintype "passive"))
    )
    (net (code "38") (name "Net-(U6-PH)") (class "Default")
      (node (ref "C17") (pin "1") (pinfunction "1_1") (pintype "passive"))
      (node (ref "D6") (pin "2") (pinfunction "2_2") (pintype "passive"))
      (node (ref "L3") (pin "1") (pinfunction "1_1") (pintype "passive"))
      (node (ref "U6") (pin "8") (pinfunction "PH_8") (pintype "passive"))
    )
    (net (code "39") (name "Net-(U6-VSNS)") (class "Default")
      (node (ref "R82") (pin "2") (pinfunction "2_2") (pintype "passive"))
      (node (ref "R83") (pin "1") (pinfunction "1_1") (pintype "passive"))
      (node (ref "U6") (pin "4") (pinfunction "VSNS_4") (pintype "passive"))
    )
    (net (code "40") (name "Net-(U7-BOOT)") (class "Default")
      (node (ref "C20") (pin "2") (pinfunction "2_2") (pintype "passive"))
      (node (ref "U7") (pin "1") (pinfunction "BOOT_1") (pintype "passive"))
    )
    (net (code "41") (name "Net-(U7-PH)") (class "Default")
      (node (ref "C20") (pin "1") (pinfunction "1_1") (pintype "passive"))
      (node (ref "D7") (pin "2") (pinfunction "2_2") (pintype "passive"))
      (node (ref "L4") (pin "1") (pinfunction "1_1") (pintype "passive"))
      (node (ref "U7") (pin "8") (pinfunction "PH_8") (pintype "passive"))
    )
    (net (code "42") (name "Net-(U7-VSNS)") (class "Default")
      (node (ref "R86") (pin "2") (pinfunction "2_2") (pintype "passive"))
      (node (ref "R87") (pin "2") (pinfunction "2_2") (pintype "passive"))
      (node (ref "U7") (pin "4") (pinfunction "VSNS_4") (pintype "passive"))
    )
    (net (code "43") (name "VIN_5V") (class "Default")
      (node (ref "C24") (pin "1") (pinfunction "1_1") (pintype "passive"))
      (node (ref "C26") (pin "1") (pinfunction "1_1") (pintype "passive"))
      (node (ref "L4") (pin "2") (pinfunction "2_2") (pintype "passive"))
      (node (ref "R87") (pin "1") (pinfunction "1_1") (pintype "passive"))
      (node (ref "U8") (pin "2") (pinfunction "Vin_2") (pintype "passive"))
    )
    (net (code "44") (name "VIN_24V") (class "Default")
      (node (ref "C12") (pin "1") (pinfunction "1_1") (pintype "passive"))
      (node (ref "C15") (pin "1") (pinfunction "1_1") (pintype "passive"))
      (node (ref "C18") (pin "1") (pinfunction "1_1") (pintype "passive"))
      (node (ref "C21") (pin "1") (pinfunction "1_1") (pintype "passive"))
      (node (ref "C22") (pin "1") (pinfunction "1_1") (pintype "passive"))
      (node (ref "JP1") (pin "1") (pinfunction "1_1") (pintype "passive"))
      (node (ref "JP2") (pin "1") (pinfunction "1_1") (pintype "passive"))
      (node (ref "U4") (pin "7") (pinfunction "VIN_7") (pintype "passive"))
      (node (ref "U5") (pin "7") (pinfunction "VIN_7") (pintype "passive"))
      (node (ref "U6") (pin "7") (pinfunction "VIN_7") (pintype "passive"))
      (node (ref "U7") (pin "7") (pinfunction "VIN_7") (pintype "passive"))
    )
    (net (code "45") (name "Vout_3V6") (class "Default")
      (node (ref "C19") (pin "1") (pinfunction "1_1") (pintype "passive"))
      (node (ref "L3") (pin "2") (pinfunction "2_2") (pintype "passive"))
      (node (ref "R80") (pin "2") (pinfunction "2_2") (pintype "passive"))
      (node (ref "R83") (pin "2") (pinfunction "2_2") (pintype "passive"))
    )
    (net (code "46") (name "Vout_7V2") (class "Default")
      (node (ref "C16") (pin "1") (pinfunction "1_1") (pintype "passive"))
      (node (ref "L2") (pin "2") (pinfunction "2_2") (pintype "passive"))
      (node (ref "R74") (pin "2") (pinfunction "2_2") (pintype "passive"))
      (node (ref "R79") (pin "2") (pinfunction "2_2") (pintype "passive"))
    )
    (net (code "47") (name "unconnected-(U4-NC-Pad2)") (class "Default")
      (node (ref "U4") (pin "2") (pinfunction "NC_2") (pintype "passive+no_connect"))
    )
    (net (code "48") (name "unconnected-(U4-NC-Pad3)") (class "Default")
      (node (ref "U4") (pin "3") (pinfunction "NC_3") (pintype "passive+no_connect"))
    )
    (net (code "49") (name "unconnected-(U5-NC-Pad2)") (class "Default")
      (node (ref "U5") (pin "2") (pinfunction "NC_2") (pintype "passive+no_connect"))
    )
    (net (code "50") (name "unconnected-(U5-NC-Pad3)") (class "Default")
      (node (ref "U5") (pin "3") (pinfunction "NC_3") (pintype "passive+no_connect"))
    )
    (net (code "51") (name "unconnected-(U6-NC-Pad2)") (class "Default")
      (node (ref "U6") (pin "2") (pinfunction "NC_2") (pintype "passive+no_connect"))
    )
    (net (code "52") (name "unconnected-(U6-NC-Pad3)") (class "Default")
      (node (ref "U6") (pin "3") (pinfunction "NC_3") (pintype "passive+no_connect"))
    )
    (net (code "53") (name "unconnected-(U7-ENA-Pad5)") (class "Default")
      (node (ref "U7") (pin "5") (pinfunction "ENA_5") (pintype "passive+no_connect"))
    )
    (net (code "54") (name "unconnected-(U7-NC-Pad2)") (class "Default")
      (node (ref "U7") (pin "2") (pinfunction "NC_2") (pintype "passive+no_connect"))
    )
    (net (code "55") (name "unconnected-(U7-NC-Pad3)") (class "Default")
      (node (ref "U7") (pin "3") (pinfunction "NC_3") (pintype "passive+no_connect"))
    )
  )
)
